# mk1.net
KiCad netlist of a schematic drawn in EAGLE
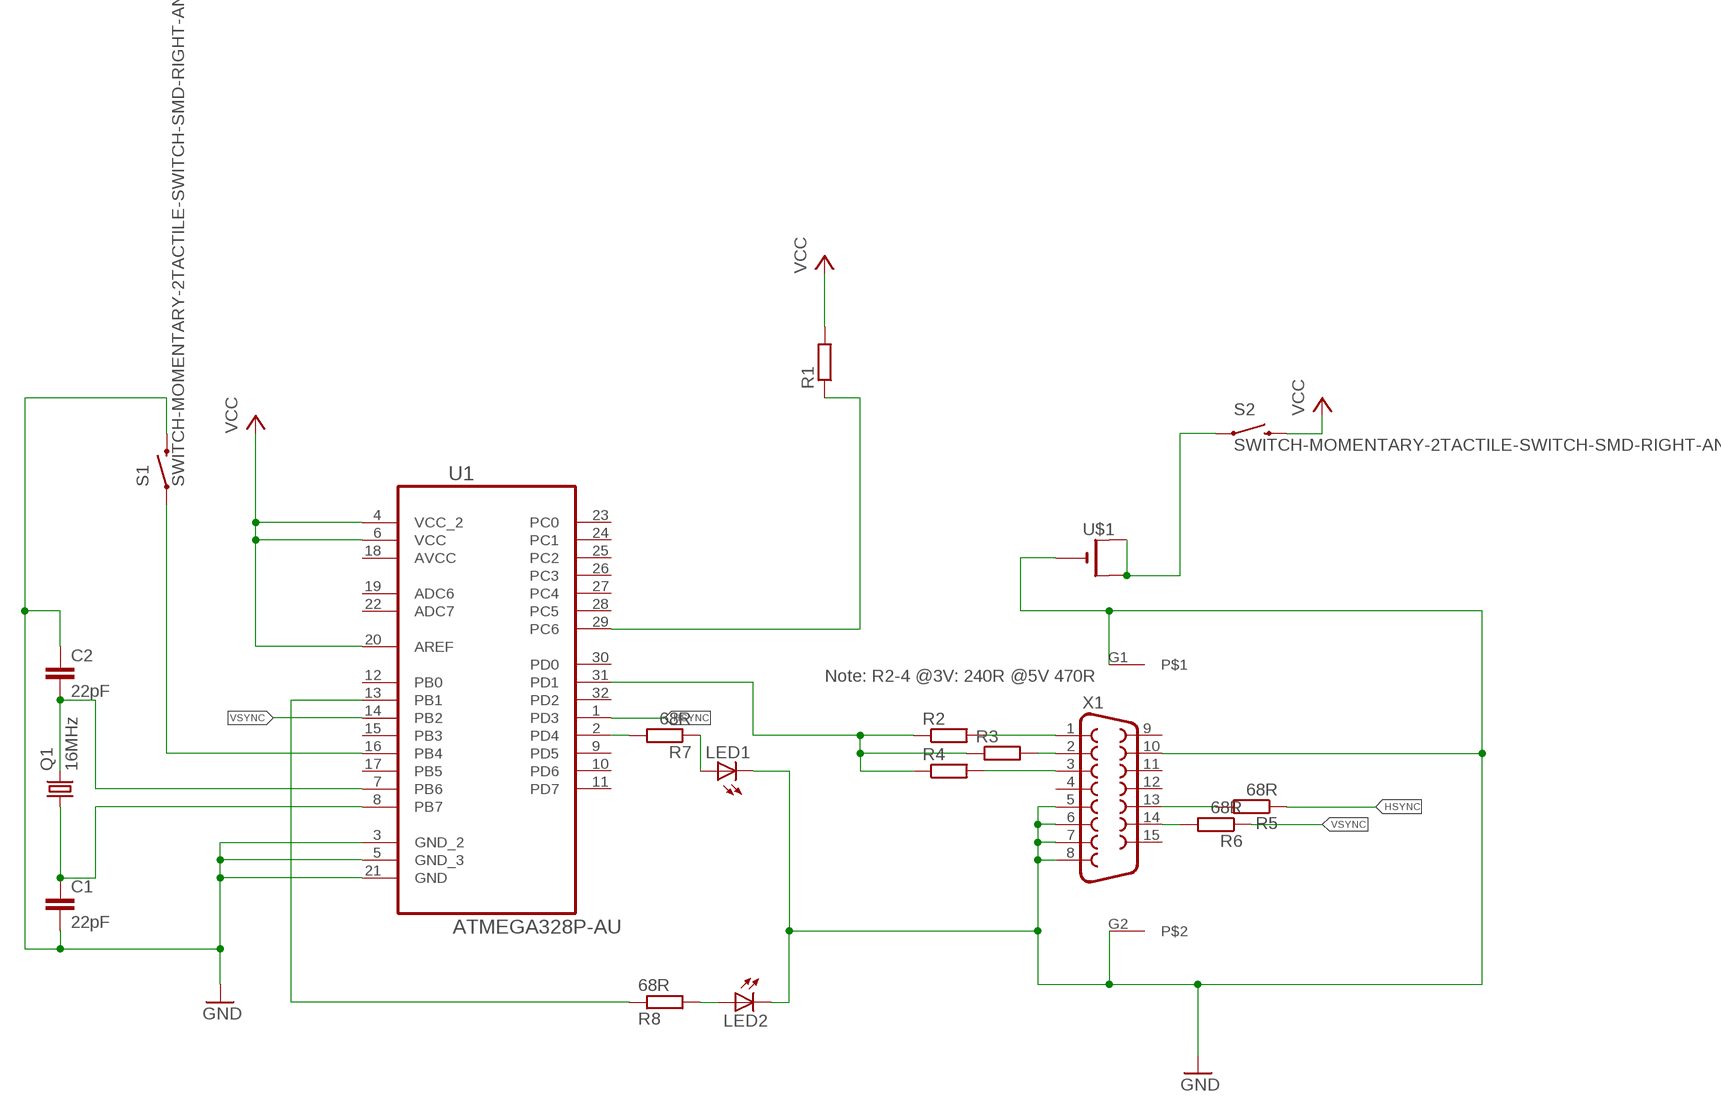
[diagram p0: schematic, sheet 1]

(export (version "E")
  (design (tool "Eeschema 10.0.6"))
  (components
    (comp (ref "C1")
      (value "22pF")
      (footprint "eagle-import:C1206")
      (libsource (lib "eagle-import") (part "C-EUC1206"))
    )
    (comp (ref "C2")
      (value "22pF")
      (footprint "eagle-import:C1206")
      (libsource (lib "eagle-import") (part "C-EUC1206"))
    )
    (comp (ref "LED1")
      (value "LEDCHIPLED_1206")
      (footprint "eagle-import:CHIPLED_1206")
      (libsource (lib "eagle-import") (part "LEDCHIPLED_1206"))
    )
    (comp (ref "LED2")
      (value "LEDCHIPLED_1206")
      (footprint "eagle-import:CHIPLED_1206")
      (libsource (lib "eagle-import") (part "LEDCHIPLED_1206"))
    )
    (comp (ref "Q1")
      (value "16MHz")
      (footprint "eagle-import:HC49UP")
      (libsource (lib "eagle-import") (part "CRYSTALHC49UP"))
    )
    (comp (ref "R1")
      (value "R-EU_M1206")
      (footprint "eagle-import:M1206")
      (libsource (lib "eagle-import") (part "R-EU_M1206"))
    )
    (comp (ref "R2")
      (value "R-EU_M1206")
      (footprint "eagle-import:M1206")
      (libsource (lib "eagle-import") (part "R-EU_M1206"))
    )
    (comp (ref "R3")
      (value "R-EU_M1206")
      (footprint "eagle-import:M1206")
      (libsource (lib "eagle-import") (part "R-EU_M1206"))
    )
    (comp (ref "R4")
      (value "R-EU_M1206")
      (footprint "eagle-import:M1206")
      (libsource (lib "eagle-import") (part "R-EU_M1206"))
    )
    (comp (ref "R5")
      (value "68R")
      (footprint "eagle-import:M1206")
      (libsource (lib "eagle-import") (part "R-EU_M1206"))
    )
    (comp (ref "R6")
      (value "68R")
      (footprint "eagle-import:M1206")
      (libsource (lib "eagle-import") (part "R-EU_M1206"))
    )
    (comp (ref "R7")
      (value "68R")
      (footprint "eagle-import:M1206")
      (libsource (lib "eagle-import") (part "R-EU_M1206"))
    )
    (comp (ref "R8")
      (value "68R")
      (footprint "eagle-import:M1206")
      (libsource (lib "eagle-import") (part "R-EU_M1206"))
    )
    (comp (ref "S1")
      (value "SWITCH-MOMENTARY-2TACTILE-SWITCH-SMD-RIGHT-ANGLE")
      (footprint "eagle-import:TACTILE_SWITCH-SMD-RIGHT-ANGLE")
      (libsource (lib "eagle-import") (part "SWITCH-MOMENTARY-2TACTILE-SWITCH-SMD-RIGHT-ANGLE"))
    )
    (comp (ref "S2")
      (value "SWITCH-MOMENTARY-2TACTILE-SWITCH-SMD-RIGHT-ANGLE")
      (footprint "eagle-import:TACTILE_SWITCH-SMD-RIGHT-ANGLE")
      (libsource (lib "eagle-import") (part "SWITCH-MOMENTARY-2TACTILE-SWITCH-SMD-RIGHT-ANGLE"))
    )
    (comp (ref "U$1")
      (value "CR2032SMT")
      (footprint "eagle-import:CR2032-SMD")
      (libsource (lib "eagle-import") (part "CR2032SMT"))
    )
    (comp (ref "U1")
      (value "ATMEGA328P-AU")
      (footprint "eagle-import:QFP80P900X900X120-32N")
      (libsource (lib "eagle-import") (part "ATMEGA328P-AU"))
    )
    (comp (ref "X1")
      (value "F15HDV")
      (footprint "eagle-import:HDF15V")
      (libsource (lib "eagle-import") (part "F15HDV"))
    )
  )
  (nets
    (net (code "1") (name "/AVCC") (class "Default")
      (node (ref "U1") (pin "18") (pinfunction "AVCC_18") (pintype "power_in"))
    )
    (net (code "2") (name "GND") (class "Default")
      (node (ref "C1") (pin "2") (pinfunction "2_2") (pintype "passive"))
      (node (ref "C2") (pin "1") (pinfunction "1_1") (pintype "passive"))
      (node (ref "LED1") (pin "C") (pinfunction "C_C") (pintype "passive"))
      (node (ref "LED2") (pin "C") (pinfunction "C_C") (pintype "passive"))
      (node (ref "S1") (pin "2") (pinfunction "2_2") (pintype "passive"))
      (node (ref "U$1") (pin "-") (pinfunction "-_-") (pintype "passive"))
      (node (ref "U1") (pin "21") (pinfunction "GND_21") (pintype "passive"))
      (node (ref "U1") (pin "3") (pinfunction "GND_2_3") (pintype "passive"))
      (node (ref "U1") (pin "5") (pinfunction "GND_3_5") (pintype "passive"))
      (node (ref "X1") (pin "10") (pinfunction "10_10") (pintype "passive"))
      (node (ref "X1") (pin "5") (pinfunction "5_5") (pintype "passive"))
      (node (ref "X1") (pin "6") (pinfunction "6_6") (pintype "passive"))
      (node (ref "X1") (pin "7") (pinfunction "7_7") (pintype "passive"))
      (node (ref "X1") (pin "8") (pinfunction "8_8") (pintype "passive"))
      (node (ref "X1") (pin "G1") (pinfunction "P$1_G1") (pintype "bidirectional"))
      (node (ref "X1") (pin "G2") (pinfunction "P$2_G2") (pintype "bidirectional"))
    )
    (net (code "3") (name "HSYNC") (class "Default")
      (node (ref "R5") (pin "1") (pinfunction "1_1") (pintype "passive"))
      (node (ref "U1") (pin "1") (pinfunction "PD3_1") (pintype "bidirectional"))
    )
    (net (code "4") (name "Net-(LED1-PadA)") (class "Default")
      (node (ref "LED1") (pin "A") (pinfunction "A_A") (pintype "passive"))
      (node (ref "R7") (pin "1") (pinfunction "1_1") (pintype "passive"))
    )
    (net (code "5") (name "Net-(LED2-PadA)") (class "Default")
      (node (ref "LED2") (pin "A") (pinfunction "A_A") (pintype "passive"))
      (node (ref "R8") (pin "2") (pinfunction "2_2") (pintype "passive"))
    )
    (net (code "6") (name "Net-(R2-Pad2)") (class "Default")
      (node (ref "R2") (pin "2") (pinfunction "2_2") (pintype "passive"))
      (node (ref "X1") (pin "1") (pinfunction "1_1") (pintype "passive"))
    )
    (net (code "7") (name "Net-(R3-Pad2)") (class "Default")
      (node (ref "R3") (pin "2") (pinfunction "2_2") (pintype "passive"))
      (node (ref "X1") (pin "2") (pinfunction "2_2") (pintype "passive"))
    )
    (net (code "8") (name "Net-(R4-Pad2)") (class "Default")
      (node (ref "R4") (pin "2") (pinfunction "2_2") (pintype "passive"))
      (node (ref "X1") (pin "3") (pinfunction "3_3") (pintype "passive"))
    )
    (net (code "9") (name "Net-(R5-Pad2)") (class "Default")
      (node (ref "R5") (pin "2") (pinfunction "2_2") (pintype "passive"))
      (node (ref "X1") (pin "13") (pinfunction "13_13") (pintype "passive"))
    )
    (net (code "10") (name "Net-(R6-Pad2)") (class "Default")
      (node (ref "R6") (pin "2") (pinfunction "2_2") (pintype "passive"))
      (node (ref "X1") (pin "14") (pinfunction "14_14") (pintype "passive"))
    )
    (net (code "11") (name "Net-(U$1-+)") (class "Default")
      (node (ref "S2") (pin "1") (pinfunction "1_1") (pintype "passive"))
      (node (ref "U$1") (pin "+$1") (pinfunction "+_+$1") (pintype "passive"))
      (node (ref "U$1") (pin "+$2") (pinfunction "+1_+$2") (pintype "passive"))
    )
    (net (code "12") (name "Net-(U1-PB1)") (class "Default")
      (node (ref "R8") (pin "1") (pinfunction "1_1") (pintype "passive"))
      (node (ref "U1") (pin "13") (pinfunction "PB1_13") (pintype "bidirectional"))
    )
    (net (code "13") (name "Net-(U1-PB4)") (class "Default")
      (node (ref "S1") (pin "1") (pinfunction "1_1") (pintype "passive"))
      (node (ref "U1") (pin "16") (pinfunction "PB4_16") (pintype "bidirectional"))
    )
    (net (code "14") (name "Net-(U1-PB6)") (class "Default")
      (node (ref "C2") (pin "2") (pinfunction "2_2") (pintype "passive"))
      (node (ref "Q1") (pin "2") (pinfunction "2_2") (pintype "passive"))
      (node (ref "U1") (pin "7") (pinfunction "PB6_7") (pintype "bidirectional"))
    )
    (net (code "15") (name "Net-(U1-PB7)") (class "Default")
      (node (ref "C1") (pin "1") (pinfunction "1_1") (pintype "passive"))
      (node (ref "Q1") (pin "1") (pinfunction "1_1") (pintype "passive"))
      (node (ref "U1") (pin "8") (pinfunction "PB7_8") (pintype "bidirectional"))
    )
    (net (code "16") (name "Net-(U1-PC6)") (class "Default")
      (node (ref "R1") (pin "1") (pinfunction "1_1") (pintype "passive"))
      (node (ref "U1") (pin "29") (pinfunction "PC6_29") (pintype "bidirectional"))
    )
    (net (code "17") (name "Net-(U1-PD1)") (class "Default")
      (node (ref "R2") (pin "1") (pinfunction "1_1") (pintype "passive"))
      (node (ref "R3") (pin "1") (pinfunction "1_1") (pintype "passive"))
      (node (ref "R4") (pin "1") (pinfunction "1_1") (pintype "passive"))
      (node (ref "U1") (pin "31") (pinfunction "PD1_31") (pintype "bidirectional"))
    )
    (net (code "18") (name "Net-(U1-PD4)") (class "Default")
      (node (ref "R7") (pin "2") (pinfunction "2_2") (pintype "passive"))
      (node (ref "U1") (pin "2") (pinfunction "PD4_2") (pintype "bidirectional"))
    )
    (net (code "19") (name "VCC") (class "Default")
      (node (ref "R1") (pin "2") (pinfunction "2_2") (pintype "passive"))
      (node (ref "S2") (pin "2") (pinfunction "2_2") (pintype "passive"))
      (node (ref "U1") (pin "20") (pinfunction "AREF_20") (pintype "input"))
      (node (ref "U1") (pin "4") (pinfunction "VCC_2_4") (pintype "power_in"))
      (node (ref "U1") (pin "6") (pinfunction "VCC_6") (pintype "power_in"))
    )
    (net (code "20") (name "VSYNC") (class "Default")
      (node (ref "R6") (pin "1") (pinfunction "1_1") (pintype "passive"))
      (node (ref "U1") (pin "14") (pinfunction "PB2_14") (pintype "bidirectional"))
    )
    (net (code "21") (name "unconnected-(U1-ADC6-Pad19)") (class "Default")
      (node (ref "U1") (pin "19") (pinfunction "ADC6_19") (pintype "input"))
    )
    (net (code "22") (name "unconnected-(U1-ADC7-Pad22)") (class "Default")
      (node (ref "U1") (pin "22") (pinfunction "ADC7_22") (pintype "input"))
    )
    (net (code "23") (name "unconnected-(U1-PB0-Pad12)") (class "Default")
      (node (ref "U1") (pin "12") (pinfunction "PB0_12") (pintype "bidirectional"))
    )
    (net (code "24") (name "unconnected-(U1-PB3-Pad15)") (class "Default")
      (node (ref "U1") (pin "15") (pinfunction "PB3_15") (pintype "bidirectional"))
    )
    (net (code "25") (name "unconnected-(U1-PB5-Pad17)") (class "Default")
      (node (ref "U1") (pin "17") (pinfunction "PB5_17") (pintype "bidirectional"))
    )
    (net (code "26") (name "unconnected-(U1-PC0-Pad23)") (class "Default")
      (node (ref "U1") (pin "23") (pinfunction "PC0_23") (pintype "bidirectional"))
    )
    (net (code "27") (name "unconnected-(U1-PC1-Pad24)") (class "Default")
      (node (ref "U1") (pin "24") (pinfunction "PC1_24") (pintype "bidirectional"))
    )
    (net (code "28") (name "unconnected-(U1-PC2-Pad25)") (class "Default")
      (node (ref "U1") (pin "25") (pinfunction "PC2_25") (pintype "bidirectional"))
    )
    (net (code "29") (name "unconnected-(U1-PC3-Pad26)") (class "Default")
      (node (ref "U1") (pin "26") (pinfunction "PC3_26") (pintype "bidirectional"))
    )
    (net (code "30") (name "unconnected-(U1-PC4-Pad27)") (class "Default")
      (node (ref "U1") (pin "27") (pinfunction "PC4_27") (pintype "bidirectional"))
    )
    (net (code "31") (name "unconnected-(U1-PC5-Pad28)") (class "Default")
      (node (ref "U1") (pin "28") (pinfunction "PC5_28") (pintype "bidirectional"))
    )
    (net (code "32") (name "unconnected-(U1-PD0-Pad30)") (class "Default")
      (node (ref "U1") (pin "30") (pinfunction "PD0_30") (pintype "bidirectional"))
    )
    (net (code "33") (name "unconnected-(U1-PD2-Pad32)") (class "Default")
      (node (ref "U1") (pin "32") (pinfunction "PD2_32") (pintype "bidirectional"))
    )
    (net (code "34") (name "unconnected-(U1-PD5-Pad9)") (class "Default")
      (node (ref "U1") (pin "9") (pinfunction "PD5_9") (pintype "bidirectional"))
    )
    (net (code "35") (name "unconnected-(U1-PD6-Pad10)") (class "Default")
      (node (ref "U1") (pin "10") (pinfunction "PD6_10") (pintype "bidirectional"))
    )
    (net (code "36") (name "unconnected-(U1-PD7-Pad11)") (class "Default")
      (node (ref "U1") (pin "11") (pinfunction "PD7_11") (pintype "bidirectional"))
    )
    (net (code "37") (name "unconnected-(X1-Pad4)") (class "Default")
      (node (ref "X1") (pin "4") (pinfunction "4_4") (pintype "passive"))
    )
    (net (code "38") (name "unconnected-(X1-Pad9)") (class "Default")
      (node (ref "X1") (pin "9") (pinfunction "9_9") (pintype "passive"))
    )
    (net (code "39") (name "unconnected-(X1-Pad11)") (class "Default")
      (node (ref "X1") (pin "11") (pinfunction "11_11") (pintype "passive"))
    )
    (net (code "40") (name "unconnected-(X1-Pad12)") (class "Default")
      (node (ref "X1") (pin "12") (pinfunction "12_12") (pintype "passive"))
    )
    (net (code "41") (name "unconnected-(X1-Pad15)") (class "Default")
      (node (ref "X1") (pin "15") (pinfunction "15_15") (pintype "passive"))
    )
  )
)
